# Input.net
KiCad netlist of a schematic drawn in Altium Designer
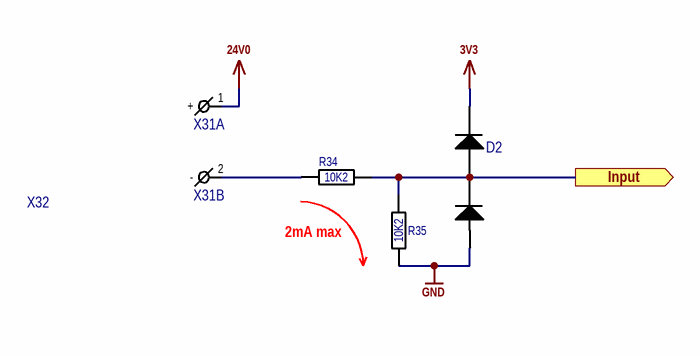
[diagram p0: Input.SchDoc]

(export (version "E")
  (design (tool "Eeschema 10.0.6"))
  (components
    (comp (ref "D2")
      (value "D")
      (footprint "SOT23-3")
      (description "DIODE ARRAY GP 70V 215MA SOT23-3")
      (fields
        (field (name "02. DISTRIBUTOR PART NUMBER") "BAV199LT1GOSDKR-ND")
        (field (name "07. MANUFACTURER  PART NUMBER") "BAV199LT1G")
        (field (name "13. CREATED DATE/NAME") "AUG 2018 / Hören")
      )
      (libsource (lib "tom") (part "BAV199L"))
    )
    (comp (ref "R34")
      (value "10K2")
      (footprint "R0603 Reflow")
      (description "RES SMD 10.2K OHM 1% 1/10W 0603")
      (fields
        (field (name "TOLERANCE") "±1%")
        (field (name "02. DISTRIBUTOR PART NUMBER") "311-10.2KHRDKR-ND")
        (field (name "13. CREATED DATE/NAME") "AUG2018/Hören")
      )
      (libsource (lib "") (part "R_1"))
    )
    (comp (ref "R35")
      (value "10K2")
      (footprint "R0603 Reflow")
      (description "RES SMD 1.62K OHM 1% 1/10W 0603")
      (fields
        (field (name "TOLERANCE") "±1%")
        (field (name "02. DISTRIBUTOR PART NUMBER") "311-1.62KHRDKR-ND")
        (field (name "13. CREATED DATE/NAME") "AUG2018/Hören")
      )
      (libsource (lib "chickenfood") (part "R"))
    )
    (comp (ref "X31")
      (value "X")
      (footprint "691322310002")
      (description "TERM BLOCK HDR 2POS 90DEG 3.81MM")
      (fields
        (field (name "02. DISTRIBUTOR PART NUMBER") "732-2088-ND")
        (field (name "07. MANUFACTURER  PART NUMBER") "691322310002")
        (field (name "13. CREATED DATE/NAME") "??? / Hören")
      )
      (libsource (lib "Connectors") (part "691322310002"))
    )
    (comp (ref "X32")
      (value "X")
      (footprint "691361300002")
      (description "TERM BLOCK PLUG 2POS STR 3.81MM")
      (fields (field (name "13. CREATED DATE/NAME") "??? / Hören"))
      (libsource (lib "Connectors") (part "691361300002"))
    )
  )
  (nets
    (net (code "1") (name "/Input") (class "Default")
      (node (ref "D2") (pin "3") (pinfunction "C/A_3") (pintype "passive"))
      (node (ref "R34") (pin "2") (pinfunction "2_2") (pintype "passive"))
      (node (ref "R35") (pin "2") (pinfunction "2_2") (pintype "passive"))
    )
    (net (code "2") (name "3V3") (class "Default")
      (node (ref "D2") (pin "2") (pinfunction "C_2") (pintype "passive"))
    )
    (net (code "3") (name "24V0") (class "Default")
      (node (ref "X31") (pin "1") (pinfunction "+_1") (pintype "passive"))
    )
    (net (code "4") (name "GND") (class "Default")
      (node (ref "D2") (pin "1") (pinfunction "A_1") (pintype "passive"))
      (node (ref "R35") (pin "1") (pinfunction "1_1") (pintype "passive"))
    )
    (net (code "5") (name "Net-(X31B--)") (class "Default")
      (node (ref "R34") (pin "1") (pinfunction "1_1") (pintype "passive"))
      (node (ref "X31") (pin "2") (pinfunction "-_2") (pintype "passive"))
    )
  )
)
